# Photon_I2C_Shield.net
KiCad netlist of a schematic drawn in EAGLE
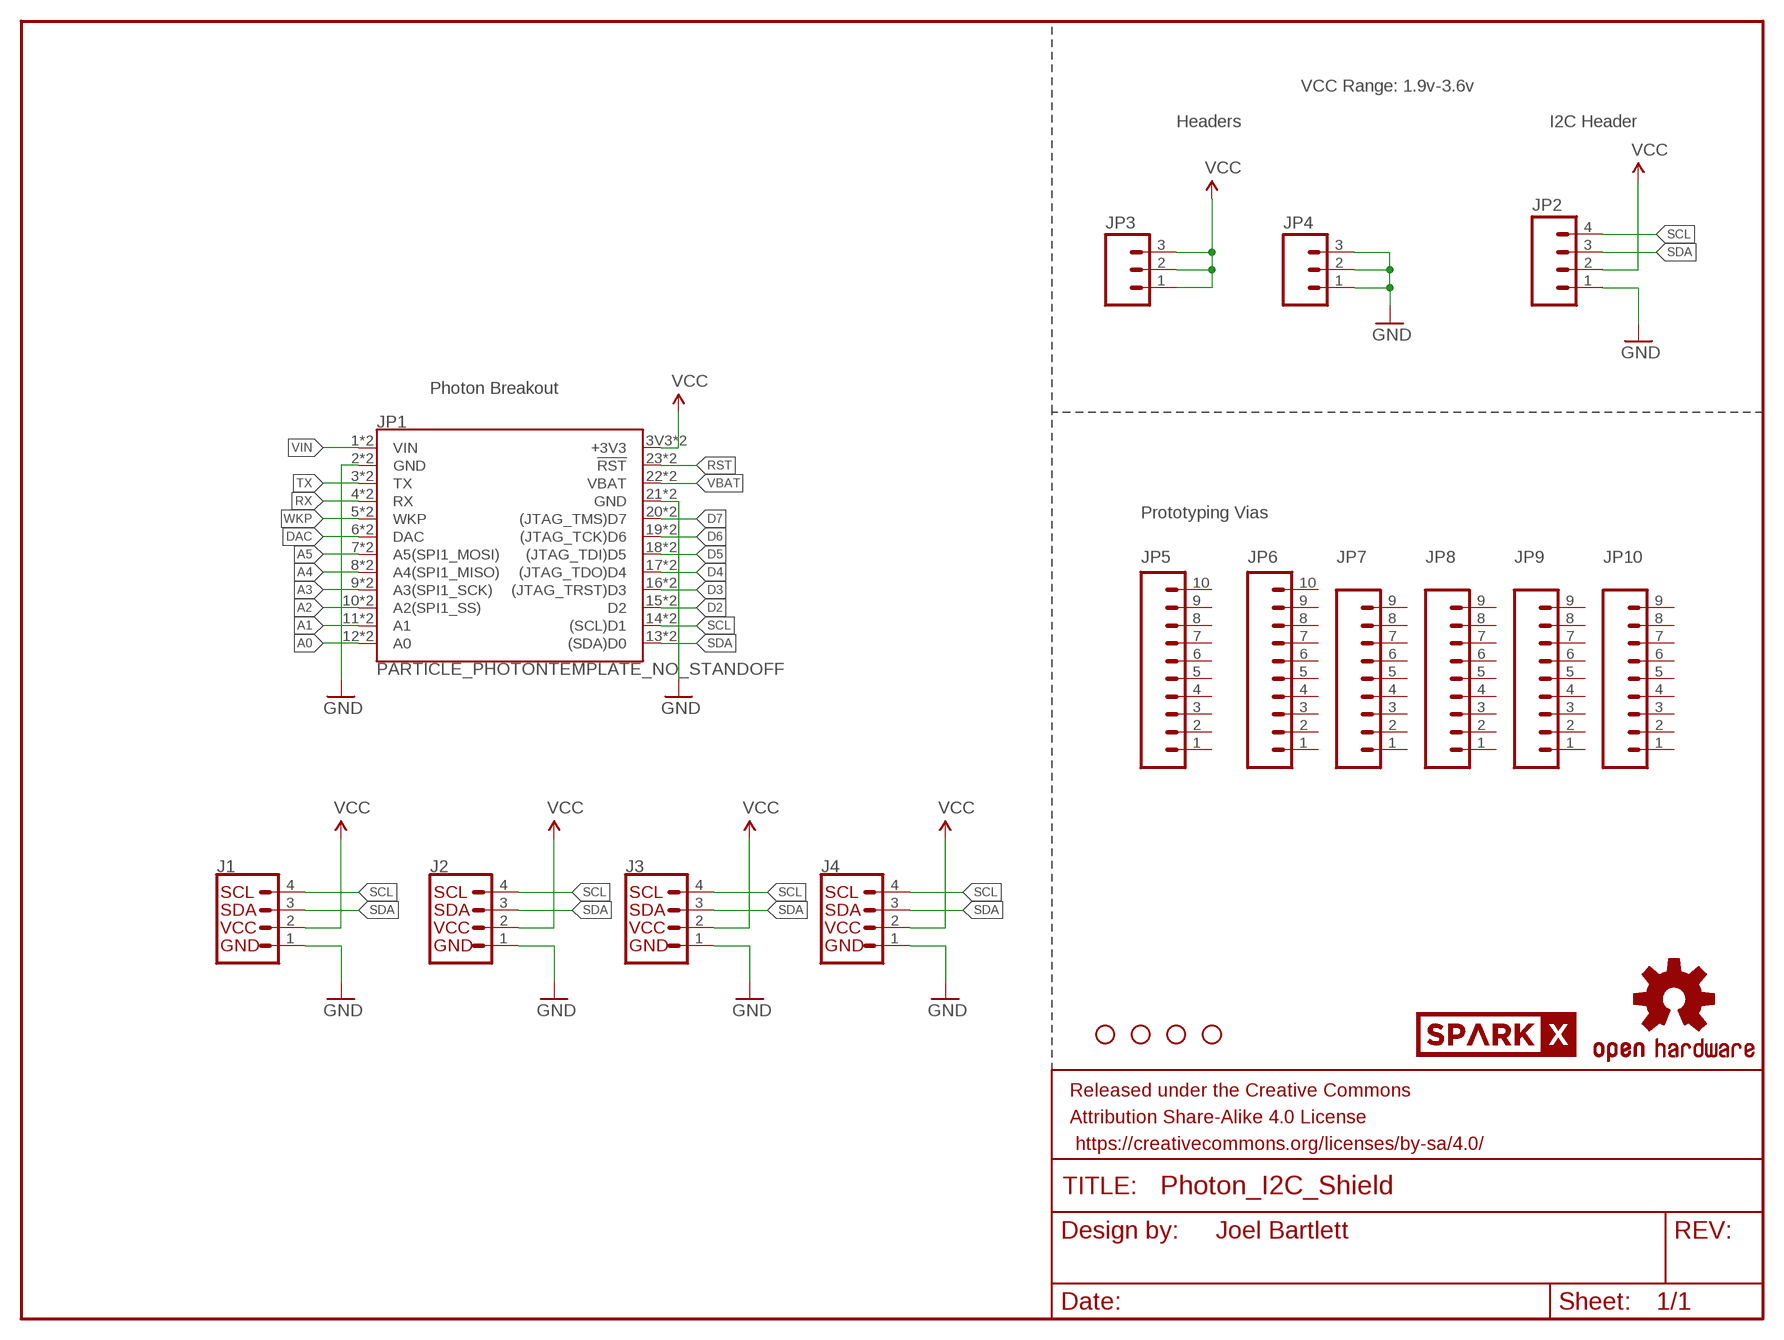
[diagram p0: schematic, sheet 1]

(export (version "E")
  (design (tool "Eeschema 10.0.6"))
  (components
    (comp (ref "FRAME1")
      (value "FRAME-LETTER")
      (footprint "eagle-import:CREATIVE_COMMONS")
      (libsource (lib "eagle-import") (part "FRAME-LETTER"))
    )
    (comp (ref "H1")
      (value "STAND-OFF")
      (footprint "eagle-import:STAND-OFF")
      (libsource (lib "eagle-import") (part "STAND-OFF"))
    )
    (comp (ref "H2")
      (value "STAND-OFF")
      (footprint "eagle-import:STAND-OFF")
      (libsource (lib "eagle-import") (part "STAND-OFF"))
    )
    (comp (ref "H3")
      (value "STAND-OFF")
      (footprint "eagle-import:STAND-OFF")
      (libsource (lib "eagle-import") (part "STAND-OFF"))
    )
    (comp (ref "H4")
      (value "STAND-OFF")
      (footprint "eagle-import:STAND-OFF")
      (libsource (lib "eagle-import") (part "STAND-OFF"))
    )
    (comp (ref "J1")
      (value "I2C_STANDARDJS-1MM")
      (footprint "eagle-import:1X04_1MM_RA")
      (libsource (lib "eagle-import") (part "I2C_STANDARDJS-1MM"))
    )
    (comp (ref "J2")
      (value "I2C_STANDARDJS-1MM")
      (footprint "eagle-import:1X04_1MM_RA")
      (libsource (lib "eagle-import") (part "I2C_STANDARDJS-1MM"))
    )
    (comp (ref "J3")
      (value "I2C_STANDARDJS-1MM")
      (footprint "eagle-import:1X04_1MM_RA")
      (libsource (lib "eagle-import") (part "I2C_STANDARDJS-1MM"))
    )
    (comp (ref "J4")
      (value "I2C_STANDARDJS-1MM")
      (footprint "eagle-import:1X04_1MM_RA")
      (libsource (lib "eagle-import") (part "I2C_STANDARDJS-1MM"))
    )
    (comp (ref "JP1")
      (value "PARTICLE_PHOTONTEMPLATE_NO_STANDOFF")
      (footprint "eagle-import:PARTICLE_PHOTON_TEMPLATE_NO_STANDOFF")
      (libsource (lib "eagle-import") (part "PARTICLE_PHOTONTEMPLATE_NO_STANDOFF"))
    )
    (comp (ref "JP2")
      (value "M04PTH")
      (footprint "eagle-import:1X04")
      (libsource (lib "eagle-import") (part "M04PTH"))
    )
    (comp (ref "JP3")
      (value "M03PTH")
      (footprint "eagle-import:1X03")
      (libsource (lib "eagle-import") (part "M03PTH"))
    )
    (comp (ref "JP4")
      (value "M03PTH")
      (footprint "eagle-import:1X03")
      (libsource (lib "eagle-import") (part "M03PTH"))
    )
    (comp (ref "JP5")
      (value "M10NO_SILK_PTH_FEMALE")
      (footprint "eagle-import:1X10_NO_SILK")
      (libsource (lib "eagle-import") (part "M10NO_SILK_PTH_FEMALE"))
    )
    (comp (ref "JP6")
      (value "M10NO_SILK_PTH_FEMALE")
      (footprint "eagle-import:1X10_NO_SILK")
      (libsource (lib "eagle-import") (part "M10NO_SILK_PTH_FEMALE"))
    )
    (comp (ref "JP7")
      (value "M09NO_SILK")
      (footprint "eagle-import:1X09_NO_SILK")
      (libsource (lib "eagle-import") (part "M09NO_SILK"))
    )
    (comp (ref "JP8")
      (value "M09NO_SILK")
      (footprint "eagle-import:1X09_NO_SILK")
      (libsource (lib "eagle-import") (part "M09NO_SILK"))
    )
    (comp (ref "JP9")
      (value "M09NO_SILK")
      (footprint "eagle-import:1X09_NO_SILK")
      (libsource (lib "eagle-import") (part "M09NO_SILK"))
    )
    (comp (ref "JP10")
      (value "M09NO_SILK")
      (footprint "eagle-import:1X09_NO_SILK")
      (libsource (lib "eagle-import") (part "M09NO_SILK"))
    )
    (comp (ref "LOGO1")
      (value "OSHW-LOGOM")
      (footprint "eagle-import:OSHW-LOGO-M")
      (libsource (lib "eagle-import") (part "OSHW-LOGOM"))
    )
    (comp (ref "U$4")
      (value "SPARKX-LOGO5")
      (footprint "eagle-import:SPARKX-LARGE")
      (libsource (lib "eagle-import") (part "SPARKX-LOGO5"))
    )
  )
  (nets
    (net (code "1") (name "A0") (class "Default")
      (node (ref "JP1") (pin "12") (pinfunction "A0_12") (pintype "bidirectional"))
      (node (ref "JP1") (pin "A0") (pinfunction "A0_A0") (pintype "bidirectional"))
    )
    (net (code "2") (name "A1") (class "Default")
      (node (ref "JP1") (pin "11") (pinfunction "A1_11") (pintype "bidirectional"))
      (node (ref "JP1") (pin "A1") (pinfunction "A1_A1") (pintype "bidirectional"))
    )
    (net (code "3") (name "A2") (class "Default")
      (node (ref "JP1") (pin "10") (pinfunction "A2(SPI1_SS)_10") (pintype "bidirectional"))
      (node (ref "JP1") (pin "A2") (pinfunction "A2(SPI1_SS)_A2") (pintype "bidirectional"))
    )
    (net (code "4") (name "A3") (class "Default")
      (node (ref "JP1") (pin "9") (pinfunction "A3(SPI1_SCK)_9") (pintype "bidirectional"))
      (node (ref "JP1") (pin "A3") (pinfunction "A3(SPI1_SCK)_A3") (pintype "bidirectional"))
    )
    (net (code "5") (name "A4") (class "Default")
      (node (ref "JP1") (pin "8") (pinfunction "A4(SPI1_MISO)_8") (pintype "bidirectional"))
      (node (ref "JP1") (pin "A4") (pinfunction "A4(SPI1_MISO)_A4") (pintype "bidirectional"))
    )
    (net (code "6") (name "A5") (class "Default")
      (node (ref "JP1") (pin "7") (pinfunction "A5(SPI1_MOSI)_7") (pintype "bidirectional"))
      (node (ref "JP1") (pin "A5") (pinfunction "A5(SPI1_MOSI)_A5") (pintype "bidirectional"))
    )
    (net (code "7") (name "D2") (class "Default")
      (node (ref "JP1") (pin "15") (pinfunction "D2_15") (pintype "bidirectional"))
      (node (ref "JP1") (pin "D2") (pinfunction "D2_D2") (pintype "bidirectional"))
    )
    (net (code "8") (name "D3") (class "Default")
      (node (ref "JP1") (pin "16") (pinfunction "(JTAG_TRST)D3_16") (pintype "bidirectional"))
      (node (ref "JP1") (pin "D3") (pinfunction "(JTAG_TRST)D3_D3") (pintype "bidirectional"))
    )
    (net (code "9") (name "D4") (class "Default")
      (node (ref "JP1") (pin "17") (pinfunction "(JTAG_TDO)D4_17") (pintype "bidirectional"))
      (node (ref "JP1") (pin "D4") (pinfunction "(JTAG_TDO)D4_D4") (pintype "bidirectional"))
    )
    (net (code "10") (name "D5") (class "Default")
      (node (ref "JP1") (pin "18") (pinfunction "(JTAG_TDI)D5_18") (pintype "bidirectional"))
      (node (ref "JP1") (pin "D5") (pinfunction "(JTAG_TDI)D5_D5") (pintype "bidirectional"))
    )
    (net (code "11") (name "D6") (class "Default")
      (node (ref "JP1") (pin "19") (pinfunction "(JTAG_TCK)D6_19") (pintype "bidirectional"))
      (node (ref "JP1") (pin "D6") (pinfunction "(JTAG_TCK)D6_D6") (pintype "bidirectional"))
    )
    (net (code "12") (name "D7") (class "Default")
      (node (ref "JP1") (pin "20") (pinfunction "(JTAG_TMS)D7_20") (pintype "bidirectional"))
      (node (ref "JP1") (pin "D7") (pinfunction "(JTAG_TMS)D7_D7") (pintype "bidirectional"))
    )
    (net (code "13") (name "DAC") (class "Default")
      (node (ref "JP1") (pin "6") (pinfunction "DAC_6") (pintype "bidirectional"))
      (node (ref "JP1") (pin "DAC") (pinfunction "DAC_DAC") (pintype "bidirectional"))
    )
    (net (code "14") (name "GND") (class "Default")
      (node (ref "J1") (pin "1") (pinfunction "GND_1") (pintype "power_in"))
      (node (ref "J2") (pin "1") (pinfunction "GND_1") (pintype "power_in"))
      (node (ref "J3") (pin "1") (pinfunction "GND_1") (pintype "power_in"))
      (node (ref "J4") (pin "1") (pinfunction "GND_1") (pintype "power_in"))
      (node (ref "JP1") (pin "2") (pinfunction "GND_2") (pintype "power_in"))
      (node (ref "JP1") (pin "21") (pinfunction "GND_21") (pintype "power_in"))
      (node (ref "JP1") (pin "GND@0") (pinfunction "GND_GND@0") (pintype "power_in"))
      (node (ref "JP1") (pin "GND@2") (pinfunction "GND_GND@2") (pintype "power_in"))
      (node (ref "JP2") (pin "1") (pinfunction "1_1") (pintype "passive"))
      (node (ref "JP4") (pin "1") (pinfunction "1_1") (pintype "passive"))
      (node (ref "JP4") (pin "2") (pinfunction "2_2") (pintype "passive"))
      (node (ref "JP4") (pin "3") (pinfunction "3_3") (pintype "passive"))
    )
    (net (code "15") (name "RST") (class "Default")
      (node (ref "JP1") (pin "23") (pinfunction "~{RST}_23") (pintype "bidirectional"))
      (node (ref "JP1") (pin "RST") (pinfunction "~{RST}_RST") (pintype "bidirectional"))
    )
    (net (code "16") (name "RX") (class "Default")
      (node (ref "JP1") (pin "4") (pinfunction "RX_4") (pintype "bidirectional"))
      (node (ref "JP1") (pin "RX") (pinfunction "RX_RX") (pintype "bidirectional"))
    )
    (net (code "17") (name "SCL") (class "Default")
      (node (ref "J1") (pin "4") (pinfunction "SCL_4") (pintype "passive"))
      (node (ref "J2") (pin "4") (pinfunction "SCL_4") (pintype "passive"))
      (node (ref "J3") (pin "4") (pinfunction "SCL_4") (pintype "passive"))
      (node (ref "J4") (pin "4") (pinfunction "SCL_4") (pintype "passive"))
      (node (ref "JP1") (pin "14") (pinfunction "(SCL)D1_14") (pintype "bidirectional"))
      (node (ref "JP1") (pin "D1") (pinfunction "(SCL)D1_D1") (pintype "bidirectional"))
      (node (ref "JP2") (pin "4") (pinfunction "4_4") (pintype "passive"))
    )
    (net (code "18") (name "SDA") (class "Default")
      (node (ref "J1") (pin "3") (pinfunction "SDA_3") (pintype "passive"))
      (node (ref "J2") (pin "3") (pinfunction "SDA_3") (pintype "passive"))
      (node (ref "J3") (pin "3") (pinfunction "SDA_3") (pintype "passive"))
      (node (ref "J4") (pin "3") (pinfunction "SDA_3") (pintype "passive"))
      (node (ref "JP1") (pin "13") (pinfunction "(SDA)D0_13") (pintype "bidirectional"))
      (node (ref "JP1") (pin "D0") (pinfunction "(SDA)D0_D0") (pintype "bidirectional"))
      (node (ref "JP2") (pin "3") (pinfunction "3_3") (pintype "passive"))
    )
    (net (code "19") (name "TX") (class "Default")
      (node (ref "JP1") (pin "3") (pinfunction "TX_3") (pintype "bidirectional"))
      (node (ref "JP1") (pin "TX") (pinfunction "TX_TX") (pintype "bidirectional"))
    )
    (net (code "20") (name "VBAT") (class "Default")
      (node (ref "JP1") (pin "22") (pinfunction "VBAT_22") (pintype "power_in"))
      (node (ref "JP1") (pin "VBAT") (pinfunction "VBAT_VBAT") (pintype "power_in"))
    )
    (net (code "21") (name "VCC") (class "Default")
      (node (ref "J1") (pin "2") (pinfunction "VCC_2") (pintype "power_in"))
      (node (ref "J2") (pin "2") (pinfunction "VCC_2") (pintype "power_in"))
      (node (ref "J3") (pin "2") (pinfunction "VCC_2") (pintype "power_in"))
      (node (ref "J4") (pin "2") (pinfunction "VCC_2") (pintype "power_in"))
      (node (ref "JP1") (pin "24") (pinfunction "+3V3_24") (pintype "power_in"))
      (node (ref "JP1") (pin "3V3") (pinfunction "+3V3_3V3") (pintype "power_in"))
      (node (ref "JP2") (pin "2") (pinfunction "2_2") (pintype "passive"))
      (node (ref "JP3") (pin "1") (pinfunction "1_1") (pintype "passive"))
      (node (ref "JP3") (pin "2") (pinfunction "2_2") (pintype "passive"))
      (node (ref "JP3") (pin "3") (pinfunction "3_3") (pintype "passive"))
    )
    (net (code "22") (name "VIN") (class "Default")
      (node (ref "JP1") (pin "1") (pinfunction "VIN_1") (pintype "power_in"))
      (node (ref "JP1") (pin "VIN") (pinfunction "VIN_VIN") (pintype "power_in"))
    )
    (net (code "23") (name "WKP") (class "Default")
      (node (ref "JP1") (pin "5") (pinfunction "WKP_5") (pintype "bidirectional"))
      (node (ref "JP1") (pin "WKP") (pinfunction "WKP_WKP") (pintype "bidirectional"))
    )
    (net (code "24") (name "unconnected-(JP5-Pad1)") (class "Default")
      (node (ref "JP5") (pin "1") (pinfunction "1_1") (pintype "passive"))
    )
    (net (code "25") (name "unconnected-(JP5-Pad2)") (class "Default")
      (node (ref "JP5") (pin "2") (pinfunction "2_2") (pintype "passive"))
    )
    (net (code "26") (name "unconnected-(JP5-Pad3)") (class "Default")
      (node (ref "JP5") (pin "3") (pinfunction "3_3") (pintype "passive"))
    )
    (net (code "27") (name "unconnected-(JP5-Pad4)") (class "Default")
      (node (ref "JP5") (pin "4") (pinfunction "4_4") (pintype "passive"))
    )
    (net (code "28") (name "unconnected-(JP5-Pad5)") (class "Default")
      (node (ref "JP5") (pin "5") (pinfunction "5_5") (pintype "passive"))
    )
    (net (code "29") (name "unconnected-(JP5-Pad6)") (class "Default")
      (node (ref "JP5") (pin "6") (pinfunction "6_6") (pintype "passive"))
    )
    (net (code "30") (name "unconnected-(JP5-Pad7)") (class "Default")
      (node (ref "JP5") (pin "7") (pinfunction "7_7") (pintype "passive"))
    )
    (net (code "31") (name "unconnected-(JP5-Pad8)") (class "Default")
      (node (ref "JP5") (pin "8") (pinfunction "8_8") (pintype "passive"))
    )
    (net (code "32") (name "unconnected-(JP5-Pad9)") (class "Default")
      (node (ref "JP5") (pin "9") (pinfunction "9_9") (pintype "passive"))
    )
    (net (code "33") (name "unconnected-(JP5-Pad10)") (class "Default")
      (node (ref "JP5") (pin "10") (pinfunction "10_10") (pintype "passive"))
    )
    (net (code "34") (name "unconnected-(JP6-Pad1)") (class "Default")
      (node (ref "JP6") (pin "1") (pinfunction "1_1") (pintype "passive"))
    )
    (net (code "35") (name "unconnected-(JP6-Pad2)") (class "Default")
      (node (ref "JP6") (pin "2") (pinfunction "2_2") (pintype "passive"))
    )
    (net (code "36") (name "unconnected-(JP6-Pad3)") (class "Default")
      (node (ref "JP6") (pin "3") (pinfunction "3_3") (pintype "passive"))
    )
    (net (code "37") (name "unconnected-(JP6-Pad4)") (class "Default")
      (node (ref "JP6") (pin "4") (pinfunction "4_4") (pintype "passive"))
    )
    (net (code "38") (name "unconnected-(JP6-Pad5)") (class "Default")
      (node (ref "JP6") (pin "5") (pinfunction "5_5") (pintype "passive"))
    )
    (net (code "39") (name "unconnected-(JP6-Pad6)") (class "Default")
      (node (ref "JP6") (pin "6") (pinfunction "6_6") (pintype "passive"))
    )
    (net (code "40") (name "unconnected-(JP6-Pad7)") (class "Default")
      (node (ref "JP6") (pin "7") (pinfunction "7_7") (pintype "passive"))
    )
    (net (code "41") (name "unconnected-(JP6-Pad8)") (class "Default")
      (node (ref "JP6") (pin "8") (pinfunction "8_8") (pintype "passive"))
    )
    (net (code "42") (name "unconnected-(JP6-Pad9)") (class "Default")
      (node (ref "JP6") (pin "9") (pinfunction "9_9") (pintype "passive"))
    )
    (net (code "43") (name "unconnected-(JP6-Pad10)") (class "Default")
      (node (ref "JP6") (pin "10") (pinfunction "10_10") (pintype "passive"))
    )
    (net (code "44") (name "unconnected-(JP7-Pad1)") (class "Default")
      (node (ref "JP7") (pin "1") (pinfunction "1_1") (pintype "passive"))
    )
    (net (code "45") (name "unconnected-(JP7-Pad2)") (class "Default")
      (node (ref "JP7") (pin "2") (pinfunction "2_2") (pintype "passive"))
    )
    (net (code "46") (name "unconnected-(JP7-Pad3)") (class "Default")
      (node (ref "JP7") (pin "3") (pinfunction "3_3") (pintype "passive"))
    )
    (net (code "47") (name "unconnected-(JP7-Pad4)") (class "Default")
      (node (ref "JP7") (pin "4") (pinfunction "4_4") (pintype "passive"))
    )
    (net (code "48") (name "unconnected-(JP7-Pad5)") (class "Default")
      (node (ref "JP7") (pin "5") (pinfunction "5_5") (pintype "passive"))
    )
    (net (code "49") (name "unconnected-(JP7-Pad6)") (class "Default")
      (node (ref "JP7") (pin "6") (pinfunction "6_6") (pintype "passive"))
    )
    (net (code "50") (name "unconnected-(JP7-Pad7)") (class "Default")
      (node (ref "JP7") (pin "7") (pinfunction "7_7") (pintype "passive"))
    )
    (net (code "51") (name "unconnected-(JP7-Pad8)") (class "Default")
      (node (ref "JP7") (pin "8") (pinfunction "8_8") (pintype "passive"))
    )
    (net (code "52") (name "unconnected-(JP7-Pad9)") (class "Default")
      (node (ref "JP7") (pin "9") (pinfunction "9_9") (pintype "passive"))
    )
    (net (code "53") (name "unconnected-(JP8-Pad1)") (class "Default")
      (node (ref "JP8") (pin "1") (pinfunction "1_1") (pintype "passive"))
    )
    (net (code "54") (name "unconnected-(JP8-Pad2)") (class "Default")
      (node (ref "JP8") (pin "2") (pinfunction "2_2") (pintype "passive"))
    )
    (net (code "55") (name "unconnected-(JP8-Pad3)") (class "Default")
      (node (ref "JP8") (pin "3") (pinfunction "3_3") (pintype "passive"))
    )
    (net (code "56") (name "unconnected-(JP8-Pad4)") (class "Default")
      (node (ref "JP8") (pin "4") (pinfunction "4_4") (pintype "passive"))
    )
    (net (code "57") (name "unconnected-(JP8-Pad5)") (class "Default")
      (node (ref "JP8") (pin "5") (pinfunction "5_5") (pintype "passive"))
    )
    (net (code "58") (name "unconnected-(JP8-Pad6)") (class "Default")
      (node (ref "JP8") (pin "6") (pinfunction "6_6") (pintype "passive"))
    )
    (net (code "59") (name "unconnected-(JP8-Pad7)") (class "Default")
      (node (ref "JP8") (pin "7") (pinfunction "7_7") (pintype "passive"))
    )
    (net (code "60") (name "unconnected-(JP8-Pad8)") (class "Default")
      (node (ref "JP8") (pin "8") (pinfunction "8_8") (pintype "passive"))
    )
    (net (code "61") (name "unconnected-(JP8-Pad9)") (class "Default")
      (node (ref "JP8") (pin "9") (pinfunction "9_9") (pintype "passive"))
    )
    (net (code "62") (name "unconnected-(JP9-Pad1)") (class "Default")
      (node (ref "JP9") (pin "1") (pinfunction "1_1") (pintype "passive"))
    )
    (net (code "63") (name "unconnected-(JP9-Pad2)") (class "Default")
      (node (ref "JP9") (pin "2") (pinfunction "2_2") (pintype "passive"))
    )
    (net (code "64") (name "unconnected-(JP9-Pad3)") (class "Default")
      (node (ref "JP9") (pin "3") (pinfunction "3_3") (pintype "passive"))
    )
    (net (code "65") (name "unconnected-(JP9-Pad4)") (class "Default")
      (node (ref "JP9") (pin "4") (pinfunction "4_4") (pintype "passive"))
    )
    (net (code "66") (name "unconnected-(JP9-Pad5)") (class "Default")
      (node (ref "JP9") (pin "5") (pinfunction "5_5") (pintype "passive"))
    )
    (net (code "67") (name "unconnected-(JP9-Pad6)") (class "Default")
      (node (ref "JP9") (pin "6") (pinfunction "6_6") (pintype "passive"))
    )
    (net (code "68") (name "unconnected-(JP9-Pad7)") (class "Default")
      (node (ref "JP9") (pin "7") (pinfunction "7_7") (pintype "passive"))
    )
    (net (code "69") (name "unconnected-(JP9-Pad8)") (class "Default")
      (node (ref "JP9") (pin "8") (pinfunction "8_8") (pintype "passive"))
    )
    (net (code "70") (name "unconnected-(JP9-Pad9)") (class "Default")
      (node (ref "JP9") (pin "9") (pinfunction "9_9") (pintype "passive"))
    )
    (net (code "71") (name "unconnected-(JP10-Pad1)") (class "Default")
      (node (ref "JP10") (pin "1") (pinfunction "1_1") (pintype "passive"))
    )
    (net (code "72") (name "unconnected-(JP10-Pad2)") (class "Default")
      (node (ref "JP10") (pin "2") (pinfunction "2_2") (pintype "passive"))
    )
    (net (code "73") (name "unconnected-(JP10-Pad3)") (class "Default")
      (node (ref "JP10") (pin "3") (pinfunction "3_3") (pintype "passive"))
    )
    (net (code "74") (name "unconnected-(JP10-Pad4)") (class "Default")
      (node (ref "JP10") (pin "4") (pinfunction "4_4") (pintype "passive"))
    )
    (net (code "75") (name "unconnected-(JP10-Pad5)") (class "Default")
      (node (ref "JP10") (pin "5") (pinfunction "5_5") (pintype "passive"))
    )
    (net (code "76") (name "unconnected-(JP10-Pad6)") (class "Default")
      (node (ref "JP10") (pin "6") (pinfunction "6_6") (pintype "passive"))
    )
    (net (code "77") (name "unconnected-(JP10-Pad7)") (class "Default")
      (node (ref "JP10") (pin "7") (pinfunction "7_7") (pintype "passive"))
    )
    (net (code "78") (name "unconnected-(JP10-Pad8)") (class "Default")
      (node (ref "JP10") (pin "8") (pinfunction "8_8") (pintype "passive"))
    )
    (net (code "79") (name "unconnected-(JP10-Pad9)") (class "Default")
      (node (ref "JP10") (pin "9") (pinfunction "9_9") (pintype "passive"))
    )
  )
)
